# Comm.net
KiCad netlist of a schematic drawn in Altium Designer
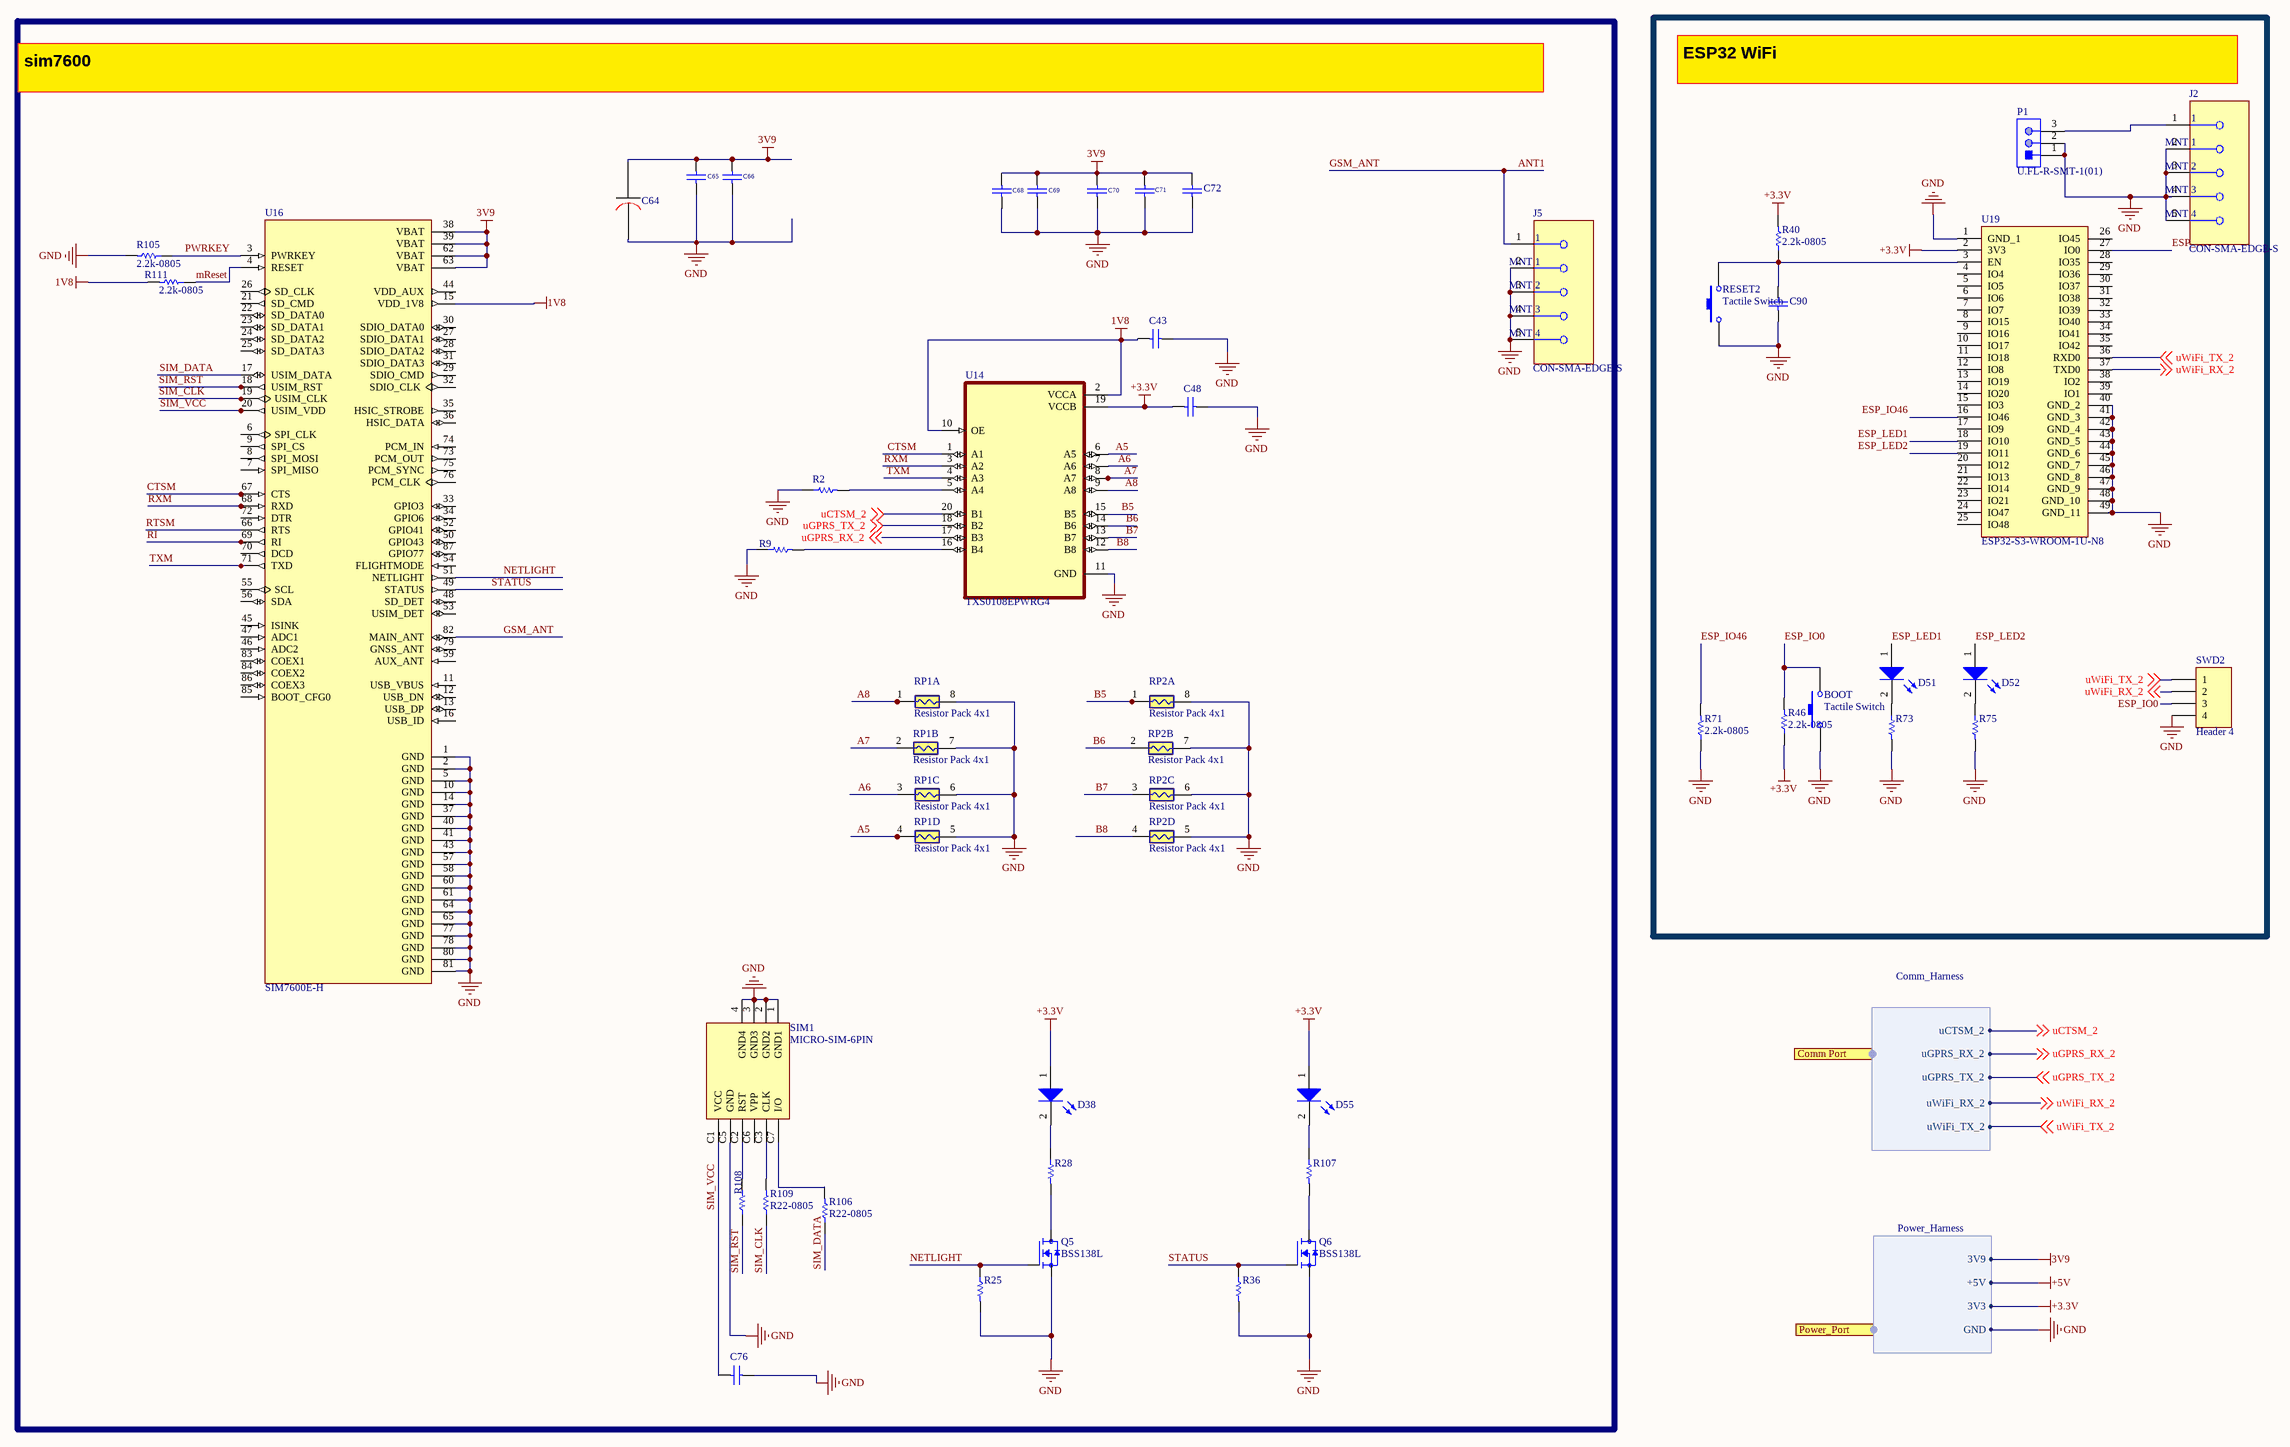
[diagram p0: Comm.SchDoc]

(export (version "E")
  (design (tool "Eeschema 10.0.6"))
  (components
    (comp (ref "BOOT")
      (value "Tactile Switch")
      (footprint "CRF06031")
      (fields (field (name "DIGI-KEY_PART_NUMBER") "732-6992-2-ND"))
      (libsource (lib "My Library") (part "Switch PB"))
    )
    (comp (ref "C43")
      (value "Cap")
      (footprint "CRF06031")
      (description "Capacitor")
      (fields (field (name "DIGI-KEY_PART_NUMBER") "490-4789-1-ND"))
      (libsource (lib "Miscellaneous Devices") (part "Cap"))
    )
    (comp (ref "C48")
      (value "Cap")
      (footprint "CRF06031")
      (description "Capacitor")
      (fields (field (name "DIGI-KEY_PART_NUMBER") "490-4789-1-ND"))
      (libsource (lib "Miscellaneous Devices") (part "Cap"))
    )
    (comp (ref "C64")
      (value "470uF-10V")
      (footprint "CAPACITOR RADIAL SMT size F")
      (description "SMD_Electrolyt")
      (fields (field (name "DIGI-KEY_PART_NUMBER") "P19732TR-ND"))
      (libsource (lib "Almas Co") (part "CAP_E_SMD"))
    )
    (comp (ref "C65")
      (value "~")
      (footprint "CRF06031")
      (description "Capacitor")
      (fields (field (name "DIGI-KEY_PART_NUMBER") "490-4789-1-ND"))
      (libsource (lib "Miscellaneous Devices") (part "Cap"))
    )
    (comp (ref "C66")
      (value "~")
      (footprint "CRF06031")
      (description "Capacitor")
      (fields (field (name "DIGI-KEY_PART_NUMBER") "490-4789-1-ND"))
      (libsource (lib "Miscellaneous Devices") (part "Cap"))
    )
    (comp (ref "C68")
      (value "~")
      (footprint "CRF06031")
      (description "Capacitor")
      (fields (field (name "DIGI-KEY_PART_NUMBER") "490-4789-1-ND"))
      (libsource (lib "Miscellaneous Devices") (part "Cap"))
    )
    (comp (ref "C69")
      (value "~")
      (footprint "CRF06031")
      (description "Capacitor")
      (fields (field (name "DIGI-KEY_PART_NUMBER") "490-4789-1-ND"))
      (libsource (lib "Miscellaneous Devices") (part "Cap"))
    )
    (comp (ref "C70")
      (value "~")
      (footprint "CRF06031")
      (description "Capacitor")
      (fields (field (name "DIGI-KEY_PART_NUMBER") "490-4789-1-ND"))
      (libsource (lib "Miscellaneous Devices") (part "Cap"))
    )
    (comp (ref "C71")
      (value "~")
      (footprint "CRF06031")
      (description "Capacitor")
      (fields (field (name "DIGI-KEY_PART_NUMBER") "490-4789-1-ND"))
      (libsource (lib "Miscellaneous Devices") (part "Cap"))
    )
    (comp (ref "C72")
      (value "~")
      (footprint "CRF06031")
      (description "Capacitor")
      (fields (field (name "DIGI-KEY_PART_NUMBER") "490-4789-1-ND"))
      (libsource (lib "Miscellaneous Devices") (part "Cap"))
    )
    (comp (ref "C76")
      (value "~")
      (footprint "CRF06031")
      (description "Capacitor")
      (fields (field (name "DIGI-KEY_PART_NUMBER") "490-4789-1-ND"))
      (libsource (lib "Miscellaneous Devices") (part "Cap"))
    )
    (comp (ref "C90")
      (value "~")
      (footprint "CRF06031")
      (description "Capacitor")
      (fields (field (name "DIGI-KEY_PART_NUMBER") "490-14464-2-ND"))
      (libsource (lib "Miscellaneous Devices") (part "Cap"))
    )
    (comp (ref "D38")
      (value "LED_0805_green")
      (footprint "0805-LED")
      (libsource (lib "HosseinLib") (part "LED_0805"))
    )
    (comp (ref "D51")
      (value "LED_0805_green")
      (footprint "0805-LED")
      (libsource (lib "HosseinLib") (part "LED_0805"))
    )
    (comp (ref "D52")
      (value "LED_0805_green")
      (footprint "0805-LED")
      (libsource (lib "HosseinLib") (part "LED_0805"))
    )
    (comp (ref "D55")
      (value "LED_0805_green")
      (footprint "0805-LED")
      (libsource (lib "HosseinLib") (part "LED_0805"))
    )
    (comp (ref "J2")
      (value "CON-SMA-EDGE-S")
      (footprint "FP-CON-SMA-EDGE-S-MFG")
      (description "CONN SMA JACK STR EDGE MNT")
      (fields
        (field (name "OCTOPART") "https://octopart.com/con-sma-edge-s-rf+solutions-70967450")
        (field (name "DIGI-KEY_PART_NUMBER") "CON-SMA-EDGE-S-ND")
      )
      (libsource (lib "Altium Content Vault") (part "a163d97a771fcdd2fd1f1a9264c171f"))
    )
    (comp (ref "J5")
      (value "CON-SMA-EDGE-S")
      (footprint "FP-CON-SMA-EDGE-S-MFG")
      (description "CONN SMA JACK STR EDGE MNT")
      (fields
        (field (name "OCTOPART") "https://octopart.com/con-sma-edge-s-rf+solutions-70967450")
        (field (name "DIGI-KEY_PART_NUMBER") "CON-SMA-EDGE-S-ND")
      )
      (libsource (lib "Altium Content Vault") (part "a163d97a771fcdd2fd1f1a9264c171f"))
    )
    (comp (ref "P1")
      (value "U.FL-R-SMT-1(01)")
      (footprint "HRS-U.FL-R-SMT-3_V")
      (description "Ultra Small Coaxial Connector, 6 GHz, -40 to 90 degC, 3-Pin SMD, RoHS, Bulk")
      (fields (field (name "DIGI-KEY_PART_NUMBER") "26-U.FL-R-SMT-1(01)-ND"))
      (libsource (lib "Altium Content Vault") (part "CN-1P-M-R3"))
    )
    (comp (ref "Q5")
      (value "BSS138L")
      (footprint "BSS138L")
      (description "smd")
      (fields (field (name "MF") "ON Semiconductor") (field (name "DIGI-KEY_PART_NUMBER") "BSS138LTR-ND"))
      (libsource (lib "BSS138L") (part "BSS138L"))
    )
    (comp (ref "Q6")
      (value "BSS138L")
      (footprint "BSS138L")
      (description "smd")
      (fields (field (name "MF") "ON Semiconductor") (field (name "DIGI-KEY_PART_NUMBER") "BSS138LTR-ND"))
      (libsource (lib "BSS138L") (part "BSS138L"))
    )
    (comp (ref "R2")
      (value "~")
      (footprint "CRF06031")
      (description "smd")
      (fields (field (name "DIGI-KEY_PART_NUMBER") "311-47.0KCRTR-ND"))
      (libsource (lib "pH_rev3") (part "ERQF06"))
    )
    (comp (ref "R9")
      (value "~")
      (footprint "CRF06031")
      (description "smd")
      (fields (field (name "DIGI-KEY_PART_NUMBER") "311-47.0KCRTR-ND"))
      (libsource (lib "pH_rev3") (part "ERQF06"))
    )
    (comp (ref "R25")
      (value "~")
      (footprint "crf06031")
      (description "smd")
      (fields (field (name "DIGI-KEY_PART_NUMBER") "311-4.70KCRTR-ND"))
      (libsource (lib "pH_rev3") (part "ERQF06"))
    )
    (comp (ref "R28")
      (value "~")
      (footprint "CRF06031")
      (description "smd")
      (fields (field (name "DIGI-KEY_PART_NUMBER") "311-4.70KCRTR-ND"))
      (libsource (lib "pH_rev3") (part "ERQF06"))
    )
    (comp (ref "R36")
      (value "~")
      (footprint "crf06031")
      (description "smd")
      (fields (field (name "DIGI-KEY_PART_NUMBER") "311-4.70KCRTR-ND"))
      (libsource (lib "pH_rev3") (part "ERQF06"))
    )
    (comp (ref "R40")
      (value "2.2k-0805")
      (footprint "CRF06031")
      (description "Resistor")
      (fields (field (name "DIGI-KEY_PART_NUMBER") "311-2.20KCRTR-ND"))
      (libsource (lib "Miscellaneous Devices") (part "Res1"))
    )
    (comp (ref "R46")
      (value "2.2k-0805")
      (footprint "CRF06031")
      (description "Resistor")
      (fields (field (name "DIGI-KEY_PART_NUMBER") "311-2.20KCRTR-ND"))
      (libsource (lib "Miscellaneous Devices") (part "Res1"))
    )
    (comp (ref "R71")
      (value "2.2k-0805")
      (footprint "CRF06031")
      (description "Resistor")
      (fields (field (name "DIGI-KEY_PART_NUMBER") "311-2.20KCRTR-ND"))
      (libsource (lib "Miscellaneous Devices") (part "Res1"))
    )
    (comp (ref "R73")
      (value "~")
      (footprint "CRF06031")
      (description "smd")
      (fields (field (name "DIGI-KEY_PART_NUMBER") "311-4.70KCRTR-ND"))
      (libsource (lib "pH_rev3") (part "ERQF06"))
    )
    (comp (ref "R75")
      (value "~")
      (footprint "CRF06031")
      (description "smd")
      (fields (field (name "DIGI-KEY_PART_NUMBER") "311-4.70KCRTR-ND"))
      (libsource (lib "pH_rev3") (part "ERQF06"))
    )
    (comp (ref "R105")
      (value "2.2k-0805")
      (footprint "CRF06031")
      (description "Resistor")
      (fields (field (name "DIGI-KEY_PART_NUMBER") "311-2.20KCRTR-ND"))
      (libsource (lib "Miscellaneous Devices") (part "Res1"))
    )
    (comp (ref "R106")
      (value "R22-0805")
      (footprint "CRF06031")
      (description "Resistor")
      (fields (field (name "DIGI-KEY_PART_NUMBER") "311-22.0CRTR-ND"))
      (libsource (lib "Miscellaneous Devices") (part "Res1"))
    )
    (comp (ref "R107")
      (value "~")
      (footprint "CRF06031")
      (description "smd")
      (fields (field (name "DIGI-KEY_PART_NUMBER") "311-4.70KCRTR-ND"))
      (libsource (lib "pH_rev3") (part "ERQF06"))
    )
    (comp (ref "R108")
      (value "R22-0805")
      (footprint "CRF06031")
      (description "Resistor")
      (fields (field (name "DIGI-KEY_PART_NUMBER") "311-22.0CRTR-ND"))
      (libsource (lib "Miscellaneous Devices") (part "Res1"))
    )
    (comp (ref "R109")
      (value "R22-0805")
      (footprint "CRF06031")
      (description "Resistor")
      (fields (field (name "DIGI-KEY_PART_NUMBER") "311-22.0CRTR-ND"))
      (libsource (lib "Miscellaneous Devices") (part "Res1"))
    )
    (comp (ref "R111")
      (value "2.2k-0805")
      (footprint "CRF06031")
      (description "Resistor")
      (fields (field (name "DIGI-KEY_PART_NUMBER") "311-2.20KCRTR-ND"))
      (libsource (lib "Miscellaneous Devices") (part "Res1"))
    )
    (comp (ref "RESET2")
      (value "Tactile Switch")
      (footprint "CRF06031")
      (fields (field (name "DIGI-KEY_PART_NUMBER") "732-6992-2-ND"))
      (libsource (lib "My Library") (part "Switch PB"))
    )
    (comp (ref "RP1")
      (value "Resistor Pack 4x1")
      (footprint "RP4x0603")
      (fields (field (name "DIGI-KEY_PART_NUMBER") "YC164J-10KTR-ND"))
      (libsource (lib "ZetaBoard_Lib") (part "Resistor Pack 4*1"))
    )
    (comp (ref "RP2")
      (value "Resistor Pack 4x1")
      (footprint "RP4x0603")
      (fields (field (name "DIGI-KEY_PART_NUMBER") "YC164J-10KTR-ND"))
      (libsource (lib "ZetaBoard_Lib") (part "Resistor Pack 4*1"))
    )
    (comp (ref "SIM1")
      (value "MICRO-SIM-6PIN")
      (footprint "MICRO-SIM-6PIN")
      (fields (field (name "DIGI-KEY_PART_NUMBER") "2223-MSIM-2-ATR-ND"))
      (libsource (lib "ZetaBoard_Lib") (part "MICRO-SIM-6PIN"))
    )
    (comp (ref "SWD2")
      (value "Header 4")
      (footprint "HDR1X4")
      (description "Header, 4-Pin")
      (libsource (lib "chilla bord") (part "Header 4"))
    )
    (comp (ref "U14")
      (value "TXS0108EPWRG4")
      (footprint "SOP65P640X120-20N")
      (fields (field (name "MF") "Texas Instruments") (field (name "DIGI-KEY_PART_NUMBER") "296-23011-2-ND"))
      (libsource (lib "TXS0108EPWRG4") (part "TXS0108EPWRG4"))
    )
    (comp (ref "U16")
      (value "SIM7600E-H")
      (footprint "IC_SIM7600E-H")
      (description "Multi-Band LTE-TDD/LTE-FDD/HSPA+ and GSM/GPRS/EDGE module")
      (fields (field (name "DIGI-KEY_PART_NUMBER") "3781-SIM7600E-H-ND"))
      (libsource (lib "SIM7600E-H") (part "SIM7600E-H"))
    )
    (comp (ref "U19")
      (value "ESP32-S3-WROOM-1U-N8")
      (footprint "SamacSys:ESP32S3WROOM1UN8")
      (description "Integrated Circuit")
      (fields
        (field (name "MOUSER PART NUMBER") "356-ESP32S3WROOM1UN8")
        (field (name "DIGI-KEY_PART_NUMBER") "1965-ESP32-S3-WROOM-1U-N8TR-ND")
      )
      (libsource (lib "*") (part "ESP32-S3-WROOM-1U-N8"))
    )
  )
  (nets
    (net (code "3") (name "+3.3V") (class "Default")
      (node (ref "C48") (pin "1") (pinfunction "1_1") (pintype "passive"))
      (node (ref "D38") (pin "1") (pinfunction "A_1") (pintype "passive"))
      (node (ref "D55") (pin "1") (pinfunction "A_1") (pintype "passive"))
      (node (ref "R40") (pin "2") (pinfunction "2_2") (pintype "passive"))
      (node (ref "R46") (pin "1") (pinfunction "1_1") (pintype "passive"))
      (node (ref "U14") (pin "19") (pinfunction "VCCB_19") (pintype "power_in"))
      (node (ref "U19") (pin "2") (pinfunction "3V3_2") (pintype "passive"))
    )
    (net (code "5") (name "/A5") (class "Default")
      (node (ref "RP1") (pin "4") (pinfunction "4_4") (pintype "passive"))
      (node (ref "U14") (pin "6") (pinfunction "A5_6") (pintype "bidirectional"))
    )
    (net (code "6") (name "/A6") (class "Default")
      (node (ref "RP1") (pin "3") (pinfunction "3_3") (pintype "passive"))
      (node (ref "U14") (pin "7") (pinfunction "A6_7") (pintype "bidirectional"))
    )
    (net (code "7") (name "/A7") (class "Default")
      (node (ref "RP1") (pin "2") (pinfunction "2_2") (pintype "passive"))
      (node (ref "U14") (pin "8") (pinfunction "A7_8") (pintype "bidirectional"))
    )
    (net (code "8") (name "/A8") (class "Default")
      (node (ref "RP1") (pin "1") (pinfunction "1_1") (pintype "passive"))
      (node (ref "U14") (pin "9") (pinfunction "A8_9") (pintype "bidirectional"))
    )
    (net (code "9") (name "/ANT1") (class "Default")
      (node (ref "J5") (pin "1") (pinfunction "1_1") (pintype "passive"))
      (node (ref "U16") (pin "82") (pinfunction "MAIN_ANT_82") (pintype "bidirectional"))
    )
    (net (code "10") (name "/B5") (class "Default")
      (node (ref "RP2") (pin "1") (pinfunction "1_1") (pintype "passive"))
      (node (ref "U14") (pin "15") (pinfunction "B5_15") (pintype "bidirectional"))
    )
    (net (code "11") (name "/B6") (class "Default")
      (node (ref "RP2") (pin "2") (pinfunction "2_2") (pintype "passive"))
      (node (ref "U14") (pin "14") (pinfunction "B6_14") (pintype "bidirectional"))
    )
    (net (code "12") (name "/B7") (class "Default")
      (node (ref "RP2") (pin "3") (pinfunction "3_3") (pintype "passive"))
      (node (ref "U14") (pin "13") (pinfunction "B7_13") (pintype "bidirectional"))
    )
    (net (code "13") (name "/B8") (class "Default")
      (node (ref "RP2") (pin "4") (pinfunction "4_4") (pintype "passive"))
      (node (ref "U14") (pin "12") (pinfunction "B8_12") (pintype "bidirectional"))
    )
    (net (code "14") (name "/CTSM") (class "Default")
      (node (ref "U14") (pin "1") (pinfunction "A1_1") (pintype "bidirectional"))
      (node (ref "U16") (pin "67") (pinfunction "CTS_67") (pintype "input"))
    )
    (net (code "15") (name "/ESP_IO0") (class "Default")
      (node (ref "BOOT") (pin "2") (pinfunction "2_2") (pintype "passive"))
      (node (ref "R46") (pin "2") (pinfunction "2_2") (pintype "passive"))
      (node (ref "SWD2") (pin "3") (pinfunction "3_3") (pintype "passive"))
      (node (ref "U19") (pin "27") (pinfunction "IO0_27") (pintype "passive"))
    )
    (net (code "16") (name "/ESP_IO46") (class "Default")
      (node (ref "R71") (pin "2") (pinfunction "2_2") (pintype "passive"))
      (node (ref "U19") (pin "16") (pinfunction "IO46_16") (pintype "passive"))
    )
    (net (code "17") (name "/ESP_LED1") (class "Default")
      (node (ref "D51") (pin "1") (pinfunction "A_1") (pintype "passive"))
      (node (ref "U19") (pin "18") (pinfunction "IO10_18") (pintype "passive"))
    )
    (net (code "18") (name "/ESP_LED2") (class "Default")
      (node (ref "D52") (pin "1") (pinfunction "A_1") (pintype "passive"))
      (node (ref "U19") (pin "19") (pinfunction "IO11_19") (pintype "passive"))
    )
    (net (code "19") (name "/NETLIGHT") (class "Default")
      (node (ref "Q5") (pin "G") (pinfunction "G_G") (pintype "passive"))
      (node (ref "R25") (pin "1") (pinfunction "1_1") (pintype "passive"))
      (node (ref "U16") (pin "51") (pinfunction "NETLIGHT_51") (pintype "output"))
    )
    (net (code "20") (name "/PWRKEY") (class "Default")
      (node (ref "R105") (pin "1") (pinfunction "1_1") (pintype "passive"))
      (node (ref "U16") (pin "3") (pinfunction "PWRKEY_3") (pintype "input"))
    )
    (net (code "21") (name "/RI") (class "Default")
      (node (ref "U16") (pin "69") (pinfunction "RI_69") (pintype "output"))
    )
    (net (code "22") (name "/RTSM") (class "Default")
      (node (ref "U16") (pin "66") (pinfunction "RTS_66") (pintype "output"))
    )
    (net (code "23") (name "/RXM") (class "Default")
      (node (ref "U14") (pin "3") (pinfunction "A2_3") (pintype "bidirectional"))
      (node (ref "U16") (pin "68") (pinfunction "RXD_68") (pintype "input"))
    )
    (net (code "24") (name "/SIM_CLK") (class "Default")
      (node (ref "R109") (pin "1") (pinfunction "1_1") (pintype "passive"))
      (node (ref "U16") (pin "19") (pinfunction "USIM_CLK_19") (pintype "output"))
    )
    (net (code "25") (name "/SIM_DATA") (class "Default")
      (node (ref "R106") (pin "1") (pinfunction "1_1") (pintype "passive"))
      (node (ref "U16") (pin "17") (pinfunction "USIM_DATA_17") (pintype "bidirectional"))
    )
    (net (code "26") (name "/SIM_RST") (class "Default")
      (node (ref "R108") (pin "1") (pinfunction "1_1") (pintype "passive"))
      (node (ref "U16") (pin "18") (pinfunction "USIM_RST_18") (pintype "output"))
    )
    (net (code "27") (name "/SIM_VCC") (class "Default")
      (node (ref "C76") (pin "2") (pinfunction "2_2") (pintype "passive"))
      (node (ref "SIM1") (pin "C1") (pinfunction "VCC_C1") (pintype "passive"))
      (node (ref "U16") (pin "20") (pinfunction "USIM_VDD_20") (pintype "output"))
    )
    (net (code "28") (name "/STATUS") (class "Default")
      (node (ref "Q6") (pin "G") (pinfunction "G_G") (pintype "passive"))
      (node (ref "R36") (pin "1") (pinfunction "1_1") (pintype "passive"))
      (node (ref "U16") (pin "49") (pinfunction "STATUS_49") (pintype "output"))
    )
    (net (code "29") (name "/TXM") (class "Default")
      (node (ref "U14") (pin "4") (pinfunction "A3_4") (pintype "bidirectional"))
      (node (ref "U16") (pin "71") (pinfunction "TXD_71") (pintype "output"))
    )
    (net (code "30") (name "/mReset") (class "Default")
      (node (ref "R111") (pin "1") (pinfunction "1_1") (pintype "passive"))
      (node (ref "U16") (pin "4") (pinfunction "RESET_4") (pintype "input"))
    )
    (net (code "33") (name "1V8") (class "Default")
      (node (ref "C43") (pin "1") (pinfunction "1_1") (pintype "passive"))
      (node (ref "R111") (pin "2") (pinfunction "2_2") (pintype "passive"))
      (node (ref "U14") (pin "10") (pinfunction "OE_10") (pintype "input"))
      (node (ref "U14") (pin "2") (pinfunction "VCCA_2") (pintype "power_in"))
      (node (ref "U16") (pin "15") (pinfunction "VDD_1V8_15") (pintype "output"))
    )
    (net (code "34") (name "3V9") (class "Default")
      (node (ref "C64") (pin "1") (pinfunction "1_1") (pintype "passive"))
      (node (ref "C65") (pin "2") (pinfunction "2_2") (pintype "passive"))
      (node (ref "C66") (pin "2") (pinfunction "2_2") (pintype "passive"))
      (node (ref "C68") (pin "2") (pinfunction "2_2") (pintype "passive"))
      (node (ref "C69") (pin "2") (pinfunction "2_2") (pintype "passive"))
      (node (ref "C70") (pin "2") (pinfunction "2_2") (pintype "passive"))
      (node (ref "C71") (pin "2") (pinfunction "2_2") (pintype "passive"))
      (node (ref "C72") (pin "2") (pinfunction "2_2") (pintype "passive"))
      (node (ref "U16") (pin "38") (pinfunction "VBAT_38") (pintype "power_in"))
      (node (ref "U16") (pin "39") (pinfunction "VBAT_39") (pintype "power_in"))
      (node (ref "U16") (pin "62") (pinfunction "VBAT_62") (pintype "power_in"))
      (node (ref "U16") (pin "63") (pinfunction "VBAT_63") (pintype "power_in"))
    )
    (net (code "35") (name "GND") (class "Default")
      (node (ref "BOOT") (pin "1") (pinfunction "1_1") (pintype "passive"))
      (node (ref "C43") (pin "2") (pinfunction "2_2") (pintype "passive"))
      (node (ref "C48") (pin "2") (pinfunction "2_2") (pintype "passive"))
      (node (ref "C64") (pin "2") (pinfunction "2_2") (pintype "passive"))
      (node (ref "C65") (pin "1") (pinfunction "1_1") (pintype "passive"))
      (node (ref "C66") (pin "1") (pinfunction "1_1") (pintype "passive"))
      (node (ref "C68") (pin "1") (pinfunction "1_1") (pintype "passive"))
      (node (ref "C69") (pin "1") (pinfunction "1_1") (pintype "passive"))
      (node (ref "C70") (pin "1") (pinfunction "1_1") (pintype "passive"))
      (node (ref "C71") (pin "1") (pinfunction "1_1") (pintype "passive"))
      (node (ref "C72") (pin "1") (pinfunction "1_1") (pintype "passive"))
      (node (ref "C76") (pin "1") (pinfunction "1_1") (pintype "passive"))
      (node (ref "C90") (pin "1") (pinfunction "1_1") (pintype "passive"))
      (node (ref "J2") (pin "2") (pinfunction "MNT_1_2") (pintype "passive"))
      (node (ref "J2") (pin "3") (pinfunction "MNT_2_3") (pintype "passive"))
      (node (ref "J2") (pin "4") (pinfunction "MNT_3_4") (pintype "passive"))
      (node (ref "J2") (pin "5") (pinfunction "MNT_4_5") (pintype "passive"))
      (node (ref "J5") (pin "2") (pinfunction "MNT_1_2") (pintype "passive"))
      (node (ref "J5") (pin "3") (pinfunction "MNT_2_3") (pintype "passive"))
      (node (ref "J5") (pin "4") (pinfunction "MNT_3_4") (pintype "passive"))
      (node (ref "J5") (pin "5") (pinfunction "MNT_4_5") (pintype "passive"))
      (node (ref "P1") (pin "1") (pinfunction "1_1") (pintype "passive"))
      (node (ref "P1") (pin "2") (pinfunction "2_2") (pintype "passive"))
      (node (ref "Q5") (pin "S") (pinfunction "S_S") (pintype "passive"))
      (node (ref "Q6") (pin "S") (pinfunction "S_S") (pintype "passive"))
      (node (ref "R105") (pin "2") (pinfunction "2_2") (pintype "passive"))
      (node (ref "R2") (pin "1") (pinfunction "1_1") (pintype "passive"))
      (node (ref "R25") (pin "2") (pinfunction "2_2") (pintype "passive"))
      (node (ref "R36") (pin "2") (pinfunction "2_2") (pintype "passive"))
      (node (ref "R71") (pin "1") (pinfunction "1_1") (pintype "passive"))
      (node (ref "R73") (pin "2") (pinfunction "2_2") (pintype "passive"))
      (node (ref "R75") (pin "2") (pinfunction "2_2") (pintype "passive"))
      (node (ref "R9") (pin "1") (pinfunction "1_1") (pintype "passive"))
      (node (ref "RESET2") (pin "1") (pinfunction "1_1") (pintype "passive"))
      (node (ref "RP1") (pin "5") (pinfunction "5_5") (pintype "passive"))
      (node (ref "RP1") (pin "6") (pinfunction "6_6") (pintype "passive"))
      (node (ref "RP1") (pin "7") (pinfunction "7_7") (pintype "passive"))
      (node (ref "RP1") (pin "8") (pinfunction "8_8") (pintype "passive"))
      (node (ref "RP2") (pin "5") (pinfunction "5_5") (pintype "passive"))
      (node (ref "RP2") (pin "6") (pinfunction "6_6") (pintype "passive"))
      (node (ref "RP2") (pin "7") (pinfunction "7_7") (pintype "passive"))
      (node (ref "RP2") (pin "8") (pinfunction "8_8") (pintype "passive"))
      (node (ref "SIM1") (pin "1") (pinfunction "GND1_1") (pintype "passive"))
      (node (ref "SIM1") (pin "2") (pinfunction "GND2_2") (pintype "passive"))
      (node (ref "SIM1") (pin "3") (pinfunction "GND3_3") (pintype "passive"))
      (node (ref "SIM1") (pin "4") (pinfunction "GND4_4") (pintype "passive"))
      (node (ref "SIM1") (pin "C5") (pinfunction "GND_C5") (pintype "passive"))
      (node (ref "SWD2") (pin "4") (pinfunction "4_4") (pintype "passive"))
      (node (ref "U14") (pin "11") (pinfunction "GND_11") (pintype "power_in"))
      (node (ref "U16") (pin "1") (pinfunction "GND_1") (pintype "power_in"))
      (node (ref "U16") (pin "10") (pinfunction "GND_10") (pintype "power_in"))
      (node (ref "U16") (pin "14") (pinfunction "GND_14") (pintype "power_in"))
      (node (ref "U16") (pin "2") (pinfunction "GND_2") (pintype "power_in"))
      (node (ref "U16") (pin "37") (pinfunction "GND_37") (pintype "power_in"))
      (node (ref "U16") (pin "40") (pinfunction "GND_40") (pintype "power_in"))
      (node (ref "U16") (pin "41") (pinfunction "GND_41") (pintype "power_in"))
      (node (ref "U16") (pin "43") (pinfunction "GND_43") (pintype "power_in"))
      (node (ref "U16") (pin "5") (pinfunction "GND_5") (pintype "power_in"))
      (node (ref "U16") (pin "57") (pinfunction "GND_57") (pintype "power_in"))
      (node (ref "U16") (pin "58") (pinfunction "GND_58") (pintype "power_in"))
      (node (ref "U16") (pin "60") (pinfunction "GND_60") (pintype "power_in"))
      (node (ref "U16") (pin "61") (pinfunction "GND_61") (pintype "power_in"))
      (node (ref "U16") (pin "64") (pinfunction "GND_64") (pintype "power_in"))
      (node (ref "U16") (pin "65") (pinfunction "GND_65") (pintype "power_in"))
      (node (ref "U16") (pin "77") (pinfunction "GND_77") (pintype "power_in"))
      (node (ref "U16") (pin "78") (pinfunction "GND_78") (pintype "power_in"))
      (node (ref "U16") (pin "80") (pinfunction "GND_80") (pintype "power_in"))
      (node (ref "U16") (pin "81") (pinfunction "GND_81") (pintype "power_in"))
      (node (ref "U19") (pin "1") (pinfunction "GND_1_1") (pintype "passive"))
      (node (ref "U19") (pin "40") (pinfunction "GND_2_40") (pintype "passive"))
      (node (ref "U19") (pin "41") (pinfunction "GND_3_41") (pintype "passive"))
      (node (ref "U19") (pin "42") (pinfunction "GND_4_42") (pintype "passive"))
      (node (ref "U19") (pin "43") (pinfunction "GND_5_43") (pintype "passive"))
      (node (ref "U19") (pin "44") (pinfunction "GND_6_44") (pintype "passive"))
      (node (ref "U19") (pin "45") (pinfunction "GND_7_45") (pintype "passive"))
      (node (ref "U19") (pin "46") (pinfunction "GND_8_46") (pintype "passive"))
      (node (ref "U19") (pin "47") (pinfunction "GND_9_47") (pintype "passive"))
      (node (ref "U19") (pin "48") (pinfunction "GND_10_48") (pintype "passive"))
      (node (ref "U19") (pin "49") (pinfunction "GND_11_49") (pintype "passive"))
    )
    (net (code "36") (name "Net-(D38-K)") (class "Default")
      (node (ref "D38") (pin "2") (pinfunction "K_2") (pintype "passive"))
      (node (ref "R28") (pin "1") (pinfunction "1_1") (pintype "passive"))
    )
    (net (code "37") (name "Net-(D51-K)") (class "Default")
      (node (ref "D51") (pin "2") (pinfunction "K_2") (pintype "passive"))
      (node (ref "R73") (pin "1") (pinfunction "1_1") (pintype "passive"))
    )
    (net (code "38") (name "Net-(D52-K)") (class "Default")
      (node (ref "D52") (pin "2") (pinfunction "K_2") (pintype "passive"))
      (node (ref "R75") (pin "1") (pinfunction "1_1") (pintype "passive"))
    )
    (net (code "39") (name "Net-(D55-K)") (class "Default")
      (node (ref "D55") (pin "2") (pinfunction "K_2") (pintype "passive"))
      (node (ref "R107") (pin "1") (pinfunction "1_1") (pintype "passive"))
    )
    (net (code "40") (name "Net-(J2-Pad1)") (class "Default")
      (node (ref "J2") (pin "1") (pinfunction "1_1") (pintype "passive"))
      (node (ref "P1") (pin "3") (pinfunction "3_3") (pintype "passive"))
    )
    (net (code "41") (name "Net-(Q5-PadD)") (class "Default")
      (node (ref "Q5") (pin "D") (pinfunction "D_D") (pintype "passive"))
      (node (ref "R28") (pin "2") (pinfunction "2_2") (pintype "passive"))
    )
    (net (code "42") (name "Net-(Q6-PadD)") (class "Default")
      (node (ref "Q6") (pin "D") (pinfunction "D_D") (pintype "passive"))
      (node (ref "R107") (pin "2") (pinfunction "2_2") (pintype "passive"))
    )
    (net (code "43") (name "Net-(SIM1-CLK)") (class "Default")
      (node (ref "R109") (pin "2") (pinfunction "2_2") (pintype "passive"))
      (node (ref "SIM1") (pin "C3") (pinfunction "CLK_C3") (pintype "passive"))
    )
    (net (code "44") (name "Net-(SIM1-I{slash}O)") (class "Default")
      (node (ref "R106") (pin "2") (pinfunction "2_2") (pintype "passive"))
      (node (ref "SIM1") (pin "C7") (pinfunction "I/O_C7") (pintype "passive"))
    )
    (net (code "45") (name "Net-(SIM1-RST)") (class "Default")
      (node (ref "R108") (pin "2") (pinfunction "2_2") (pintype "passive"))
      (node (ref "SIM1") (pin "C2") (pinfunction "RST_C2") (pintype "passive"))
    )
    (net (code "46") (name "Net-(U14-A4)") (class "Default")
      (node (ref "R2") (pin "2") (pinfunction "2_2") (pintype "passive"))
      (node (ref "U14") (pin "5") (pinfunction "A4_5") (pintype "bidirectional"))
    )
    (net (code "47") (name "Net-(U14-B4)") (class "Default")
      (node (ref "R9") (pin "2") (pinfunction "2_2") (pintype "passive"))
      (node (ref "U14") (pin "16") (pinfunction "B4_16") (pintype "bidirectional"))
    )
    (net (code "48") (name "Net-(U19-EN)") (class "Default")
      (node (ref "C90") (pin "2") (pinfunction "2_2") (pintype "passive"))
      (node (ref "R40") (pin "1") (pinfunction "1_1") (pintype "passive"))
      (node (ref "RESET2") (pin "2") (pinfunction "2_2") (pintype "passive"))
      (node (ref "U19") (pin "3") (pinfunction "EN_3") (pintype "passive"))
    )
    (net (code "49") (name "uCTSM_2") (class "Default")
      (node (ref "U14") (pin "20") (pinfunction "B1_20") (pintype "bidirectional"))
    )
    (net (code "50") (name "uGPRS_RX_2") (class "Default")
      (node (ref "U14") (pin "17") (pinfunction "B3_17") (pintype "bidirectional"))
    )
    (net (code "51") (name "uGPRS_TX_2") (class "Default")
      (node (ref "U14") (pin "18") (pinfunction "B2_18") (pintype "bidirectional"))
    )
    (net (code "52") (name "uWiFi_RX_2") (class "Default")
      (node (ref "SWD2") (pin "2") (pinfunction "2_2") (pintype "passive"))
      (node (ref "U19") (pin "37") (pinfunction "TXD0_37") (pintype "passive"))
    )
    (net (code "53") (name "uWiFi_TX_2") (class "Default")
      (node (ref "SWD2") (pin "1") (pinfunction "1_1") (pintype "passive"))
      (node (ref "U19") (pin "36") (pinfunction "RXD0_36") (pintype "passive"))
    )
    (net (code "54") (name "unconnected-(SIM1-VPP-PadC6)") (class "Default")
      (node (ref "SIM1") (pin "C6") (pinfunction "VPP_C6") (pintype "passive"))
    )
    (net (code "55") (name "unconnected-(U16-ADC1-Pad47)") (class "Default")
      (node (ref "U16") (pin "47") (pinfunction "ADC1_47") (pintype "input"))
    )
    (net (code "56") (name "unconnected-(U16-ADC2-Pad46)") (class "Default")
      (node (ref "U16") (pin "46") (pinfunction "ADC2_46") (pintype "input"))
    )
    (net (code "57") (name "unconnected-(U16-AUX_ANT-Pad59)") (class "Default")
      (node (ref "U16") (pin "59") (pinfunction "AUX_ANT_59") (pintype "input"))
    )
    (net (code "58") (name "unconnected-(U16-BOOT_CFG0-Pad85)") (class "Default")
      (node (ref "U16") (pin "85") (pinfunction "BOOT_CFG0_85") (pintype "input"))
    )
    (net (code "59") (name "unconnected-(U16-COEX1-Pad83)") (class "Default")
      (node (ref "U16") (pin "83") (pinfunction "COEX1_83") (pintype "bidirectional"))
    )
    (net (code "60") (name "unconnected-(U16-COEX2-Pad84)") (class "Default")
      (node (ref "U16") (pin "84") (pinfunction "COEX2_84") (pintype "bidirectional"))
    )
    (net (code "61") (name "unconnected-(U16-COEX3-Pad86)") (class "Default")
      (node (ref "U16") (pin "86") (pinfunction "COEX3_86") (pintype "bidirectional"))
    )
    (net (code "62") (name "unconnected-(U16-DCD-Pad70)") (class "Default")
      (node (ref "U16") (pin "70") (pinfunction "DCD_70") (pintype "output"))
    )
    (net (code "63") (name "unconnected-(U16-DTR-Pad72)") (class "Default")
      (node (ref "U16") (pin "72") (pinfunction "DTR_72") (pintype "input"))
    )
    (net (code "64") (name "unconnected-(U16-FLIGHTMODE-Pad54)") (class "Default")
      (node (ref "U16") (pin "54") (pinfunction "FLIGHTMODE_54") (pintype "input"))
    )
    (net (code "65") (name "unconnected-(U16-GNSS_ANT-Pad79)") (class "Default")
      (node (ref "U16") (pin "79") (pinfunction "GNSS_ANT_79") (pintype "bidirectional"))
    )
    (net (code "66") (name "unconnected-(U16-GPIO3-Pad33)") (class "Default")
      (node (ref "U16") (pin "33") (pinfunction "GPIO3_33") (pintype "bidirectional"))
    )
    (net (code "67") (name "unconnected-(U16-GPIO6-Pad34)") (class "Default")
      (node (ref "U16") (pin "34") (pinfunction "GPIO6_34") (pintype "bidirectional"))
    )
    (net (code "68") (name "unconnected-(U16-GPIO41-Pad52)") (class "Default")
      (node (ref "U16") (pin "52") (pinfunction "GPIO41_52") (pintype "bidirectional"))
    )
    (net (code "69") (name "unconnected-(U16-GPIO43-Pad50)") (class "Default")
      (node (ref "U16") (pin "50") (pinfunction "GPIO43_50") (pintype "bidirectional"))
    )
    (net (code "70") (name "unconnected-(U16-GPIO77-Pad87)") (class "Default")
      (node (ref "U16") (pin "87") (pinfunction "GPIO77_87") (pintype "bidirectional"))
    )
    (net (code "71") (name "unconnected-(U16-HSIC_DATA-Pad36)") (class "Default")
      (node (ref "U16") (pin "36") (pinfunction "HSIC_DATA_36") (pintype "bidirectional"))
    )
    (net (code "72") (name "unconnected-(U16-HSIC_STROBE-Pad35)") (class "Default")
      (node (ref "U16") (pin "35") (pinfunction "HSIC_STROBE_35") (pintype "output"))
    )
    (net (code "73") (name "unconnected-(U16-ISINK-Pad45)") (class "Default")
      (node (ref "U16") (pin "45") (pinfunction "ISINK_45") (pintype "input"))
    )
    (net (code "74") (name "unconnected-(U16-PCM_CLK-Pad76)") (class "Default")
      (node (ref "U16") (pin "76") (pinfunction "PCM_CLK_76") (pintype "output"))
    )
    (net (code "75") (name "unconnected-(U16-PCM_IN-Pad74)") (class "Default")
      (node (ref "U16") (pin "74") (pinfunction "PCM_IN_74") (pintype "input"))
    )
    (net (code "76") (name "unconnected-(U16-PCM_OUT-Pad73)") (class "Default")
      (node (ref "U16") (pin "73") (pinfunction "PCM_OUT_73") (pintype "output"))
    )
    (net (code "77") (name "unconnected-(U16-PCM_SYNC-Pad75)") (class "Default")
      (node (ref "U16") (pin "75") (pinfunction "PCM_SYNC_75") (pintype "output"))
    )
    (net (code "78") (name "unconnected-(U16-SCL-Pad55)") (class "Default")
      (node (ref "U16") (pin "55") (pinfunction "SCL_55") (pintype "output"))
    )
    (net (code "79") (name "unconnected-(U16-SDA-Pad56)") (class "Default")
      (node (ref "U16") (pin "56") (pinfunction "SDA_56") (pintype "bidirectional"))
    )
    (net (code "80") (name "unconnected-(U16-SDIO_CLK-Pad32)") (class "Default")
      (node (ref "U16") (pin "32") (pinfunction "SDIO_CLK_32") (pintype "output"))
    )
    (net (code "81") (name "unconnected-(U16-SDIO_CMD-Pad29)") (class "Default")
      (node (ref "U16") (pin "29") (pinfunction "SDIO_CMD_29") (pintype "output"))
    )
    (net (code "82") (name "unconnected-(U16-SDIO_DATA0-Pad30)") (class "Default")
      (node (ref "U16") (pin "30") (pinfunction "SDIO_DATA0_30") (pintype "bidirectional"))
    )
    (net (code "83") (name "unconnected-(U16-SDIO_DATA1-Pad27)") (class "Default")
      (node (ref "U16") (pin "27") (pinfunction "SDIO_DATA1_27") (pintype "bidirectional"))
    )
    (net (code "84") (name "unconnected-(U16-SDIO_DATA2-Pad28)") (class "Default")
      (node (ref "U16") (pin "28") (pinfunction "SDIO_DATA2_28") (pintype "bidirectional"))
    )
    (net (code "85") (name "unconnected-(U16-SDIO_DATA3-Pad31)") (class "Default")
      (node (ref "U16") (pin "31") (pinfunction "SDIO_DATA3_31") (pintype "bidirectional"))
    )
    (net (code "86") (name "unconnected-(U16-SD_CLK-Pad26)") (class "Default")
      (node (ref "U16") (pin "26") (pinfunction "SD_CLK_26") (pintype "output"))
    )
    (net (code "87") (name "unconnected-(U16-SD_CMD-Pad21)") (class "Default")
      (node (ref "U16") (pin "21") (pinfunction "SD_CMD_21") (pintype "output"))
    )
    (net (code "88") (name "unconnected-(U16-SD_DATA0-Pad22)") (class "Default")
      (node (ref "U16") (pin "22") (pinfunction "SD_DATA0_22") (pintype "bidirectional"))
    )
    (net (code "89") (name "unconnected-(U16-SD_DATA1-Pad23)") (class "Default")
      (node (ref "U16") (pin "23") (pinfunction "SD_DATA1_23") (pintype "bidirectional"))
    )
    (net (code "90") (name "unconnected-(U16-SD_DATA2-Pad24)") (class "Default")
      (node (ref "U16") (pin "24") (pinfunction "SD_DATA2_24") (pintype "bidirectional"))
    )
    (net (code "91") (name "unconnected-(U16-SD_DATA3-Pad25)") (class "Default")
      (node (ref "U16") (pin "25") (pinfunction "SD_DATA3_25") (pintype "bidirectional"))
    )
    (net (code "92") (name "unconnected-(U16-SD_DET-Pad48)") (class "Default")
      (node (ref "U16") (pin "48") (pinfunction "SD_DET_48") (pintype "bidirectional"))
    )
    (net (code "93") (name "unconnected-(U16-SPI_CLK-Pad6)") (class "Default")
      (node (ref "U16") (pin "6") (pinfunction "SPI_CLK_6") (pintype "output"))
    )
    (net (code "94") (name "unconnected-(U16-SPI_CS-Pad9)") (class "Default")
      (node (ref "U16") (pin "9") (pinfunction "SPI_CS_9") (pintype "output"))
    )
    (net (code "95") (name "unconnected-(U16-SPI_MISO-Pad7)") (class "Default")
      (node (ref "U16") (pin "7") (pinfunction "SPI_MISO_7") (pintype "input"))
    )
    (net (code "96") (name "unconnected-(U16-SPI_MOSI-Pad8)") (class "Default")
      (node (ref "U16") (pin "8") (pinfunction "SPI_MOSI_8") (pintype "output"))
    )
    (net (code "97") (name "unconnected-(U16-USB_DN-Pad12)") (class "Default")
      (node (ref "U16") (pin "12") (pinfunction "USB_DN_12") (pintype "bidirectional"))
    )
    (net (code "98") (name "unconnected-(U16-USB_DP-Pad13)") (class "Default")
      (node (ref "U16") (pin "13") (pinfunction "USB_DP_13") (pintype "bidirectional"))
    )
    (net (code "99") (name "unconnected-(U16-USB_ID-Pad16)") (class "Default")
      (node (ref "U16") (pin "16") (pinfunction "USB_ID_16") (pintype "input"))
    )
    (net (code "100") (name "unconnected-(U16-USB_VBUS-Pad11)") (class "Default")
      (node (ref "U16") (pin "11") (pinfunction "USB_VBUS_11") (pintype "input"))
    )
    (net (code "101") (name "unconnected-(U16-USIM_DET-Pad53)") (class "Default")
      (node (ref "U16") (pin "53") (pinfunction "USIM_DET_53") (pintype "bidirectional"))
    )
    (net (code "102") (name "unconnected-(U16-VDD_AUX-Pad44)") (class "Default")
      (node (ref "U16") (pin "44") (pinfunction "VDD_AUX_44") (pintype "output"))
    )
    (net (code "103") (name "unconnected-(U19-IO1-Pad39)") (class "Default")
      (node (ref "U19") (pin "39") (pinfunction "IO1_39") (pintype "passive"))
    )
    (net (code "104") (name "unconnected-(U19-IO2-Pad38)") (class "Default")
      (node (ref "U19") (pin "38") (pinfunction "IO2_38") (pintype "passive"))
    )
    (net (code "105") (name "unconnected-(U19-IO3-Pad15)") (class "Default")
      (node (ref "U19") (pin "15") (pinfunction "IO3_15") (pintype "passive"))
    )
    (net (code "106") (name "unconnected-(U19-IO4-Pad4)") (class "Default")
      (node (ref "U19") (pin "4") (pinfunction "IO4_4") (pintype "passive"))
    )
    (net (code "107") (name "unconnected-(U19-IO5-Pad5)") (class "Default")
      (node (ref "U19") (pin "5") (pinfunction "IO5_5") (pintype "passive"))
    )
    (net (code "108") (name "unconnected-(U19-IO6-Pad6)") (class "Default")
      (node (ref "U19") (pin "6") (pinfunction "IO6_6") (pintype "passive"))
    )
    (net (code "109") (name "unconnected-(U19-IO7-Pad7)") (class "Default")
      (node (ref "U19") (pin "7") (pinfunction "IO7_7") (pintype "passive"))
    )
    (net (code "110") (name "unconnected-(U19-IO8-Pad12)") (class "Default")
      (node (ref "U19") (pin "12") (pinfunction "IO8_12") (pintype "passive"))
    )
    (net (code "111") (name "unconnected-(U19-IO9-Pad17)") (class "Default")
      (node (ref "U19") (pin "17") (pinfunction "IO9_17") (pintype "passive"))
    )
    (net (code "112") (name "unconnected-(U19-IO12-Pad20)") (class "Default")
      (node (ref "U19") (pin "20") (pinfunction "IO12_20") (pintype "passive"))
    )
    (net (code "113") (name "unconnected-(U19-IO13-Pad21)") (class "Default")
      (node (ref "U19") (pin "21") (pinfunction "IO13_21") (pintype "passive"))
    )
    (net (code "114") (name "unconnected-(U19-IO14-Pad22)") (class "Default")
      (node (ref "U19") (pin "22") (pinfunction "IO14_22") (pintype "passive"))
    )
    (net (code "115") (name "unconnected-(U19-IO15-Pad8)") (class "Default")
      (node (ref "U19") (pin "8") (pinfunction "IO15_8") (pintype "passive"))
    )
    (net (code "116") (name "unconnected-(U19-IO16-Pad9)") (class "Default")
      (node (ref "U19") (pin "9") (pinfunction "IO16_9") (pintype "passive"))
    )
    (net (code "117") (name "unconnected-(U19-IO17-Pad10)") (class "Default")
      (node (ref "U19") (pin "10") (pinfunction "IO17_10") (pintype "passive"))
    )
    (net (code "118") (name "unconnected-(U19-IO18-Pad11)") (class "Default")
      (node (ref "U19") (pin "11") (pinfunction "IO18_11") (pintype "passive"))
    )
    (net (code "119") (name "unconnected-(U19-IO19-Pad13)") (class "Default")
      (node (ref "U19") (pin "13") (pinfunction "IO19_13") (pintype "passive"))
    )
    (net (code "120") (name "unconnected-(U19-IO20-Pad14)") (class "Default")
      (node (ref "U19") (pin "14") (pinfunction "IO20_14") (pintype "passive"))
    )
    (net (code "121") (name "unconnected-(U19-IO21-Pad23)") (class "Default")
      (node (ref "U19") (pin "23") (pinfunction "IO21_23") (pintype "passive"))
    )
    (net (code "122") (name "unconnected-(U19-IO35-Pad28)") (class "Default")
      (node (ref "U19") (pin "28") (pinfunction "IO35_28") (pintype "passive"))
    )
    (net (code "123") (name "unconnected-(U19-IO36-Pad29)") (class "Default")
      (node (ref "U19") (pin "29") (pinfunction "IO36_29") (pintype "passive"))
    )
    (net (code "124") (name "unconnected-(U19-IO37-Pad30)") (class "Default")
      (node (ref "U19") (pin "30") (pinfunction "IO37_30") (pintype "passive"))
    )
    (net (code "125") (name "unconnected-(U19-IO38-Pad31)") (class "Default")
      (node (ref "U19") (pin "31") (pinfunction "IO38_31") (pintype "passive"))
    )
    (net (code "126") (name "unconnected-(U19-IO39-Pad32)") (class "Default")
      (node (ref "U19") (pin "32") (pinfunction "IO39_32") (pintype "passive"))
    )
    (net (code "127") (name "unconnected-(U19-IO40-Pad33)") (class "Default")
      (node (ref "U19") (pin "33") (pinfunction "IO40_33") (pintype "passive"))
    )
    (net (code "128") (name "unconnected-(U19-IO41-Pad34)") (class "Default")
      (node (ref "U19") (pin "34") (pinfunction "IO41_34") (pintype "passive"))
    )
    (net (code "129") (name "unconnected-(U19-IO42-Pad35)") (class "Default")
      (node (ref "U19") (pin "35") (pinfunction "IO42_35") (pintype "passive"))
    )
    (net (code "130") (name "unconnected-(U19-IO45-Pad26)") (class "Default")
      (node (ref "U19") (pin "26") (pinfunction "IO45_26") (pintype "passive"))
    )
    (net (code "131") (name "unconnected-(U19-IO47-Pad24)") (class "Default")
      (node (ref "U19") (pin "24") (pinfunction "IO47_24") (pintype "passive"))
    )
    (net (code "132") (name "unconnected-(U19-IO48-Pad25)") (class "Default")
      (node (ref "U19") (pin "25") (pinfunction "IO48_25") (pintype "passive"))
    )
  )
)
